# PMIC.net
KiCad netlist of a schematic drawn in Altium Designer
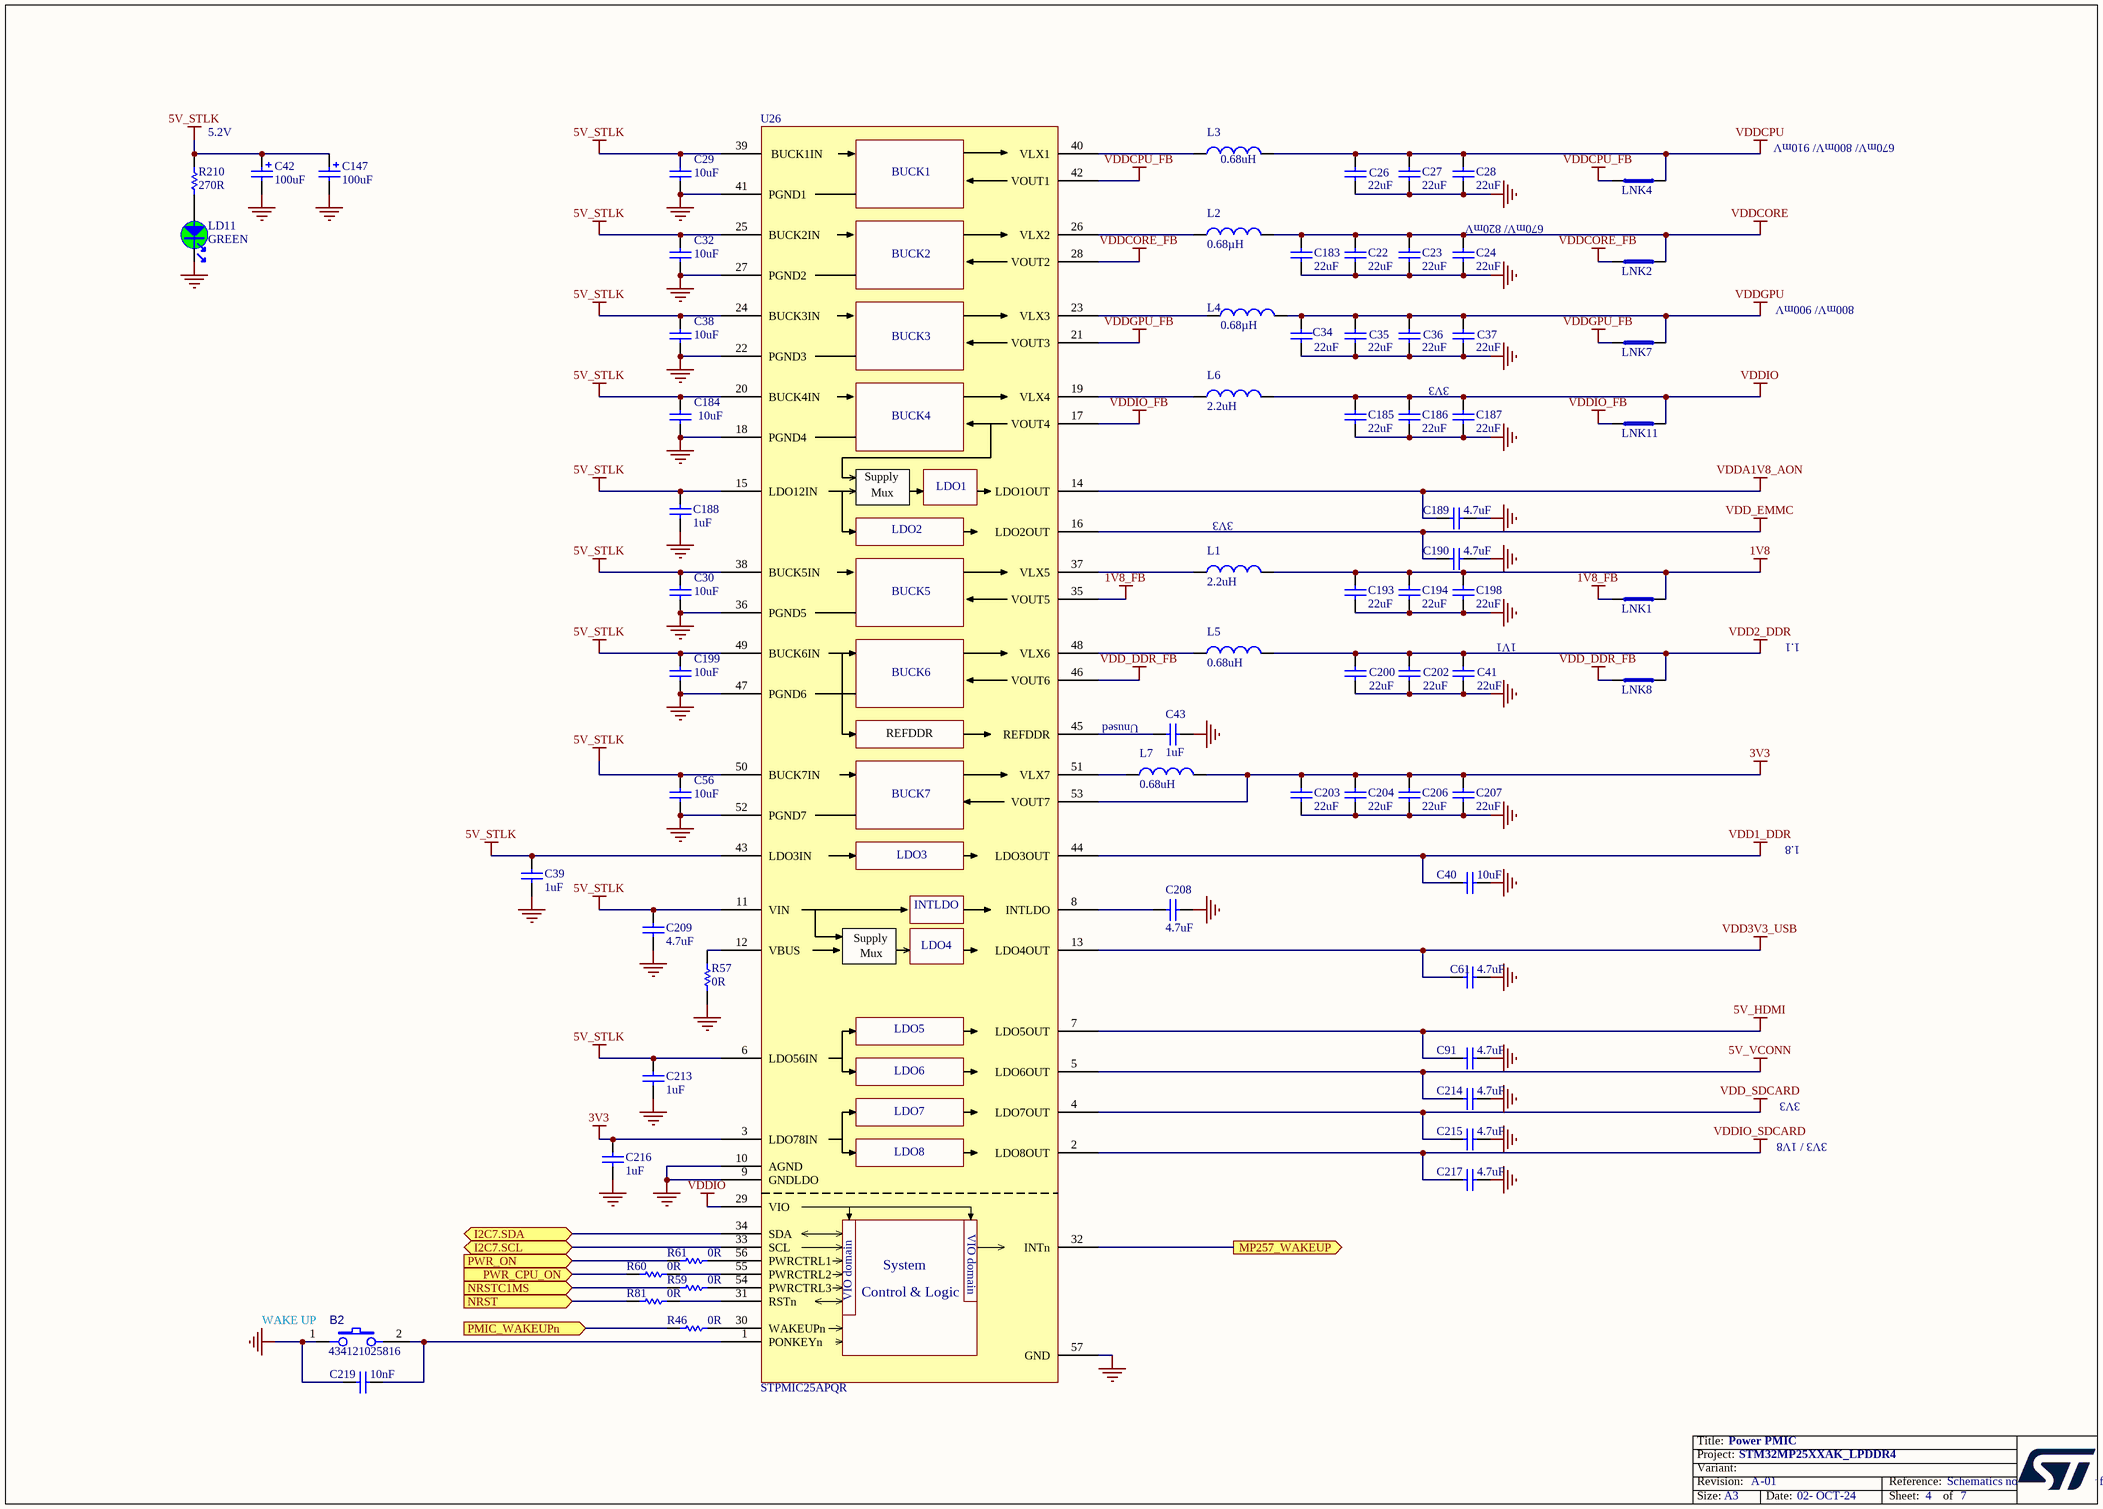
[diagram p0: PMIC.SchDoc]

(export (version "E")
  (design (tool "Eeschema 10.0.6"))
  (components
    (comp (ref "B2")
      (value "434121025816")
      (footprint "SWI_WE_434121025816")
      (description "Switch tactile, SPST-NO, 50mA, 12V, 6x3.8mm")
      (fields
        (field (name "INTERNAL_PART_NUMBER") "MCD-03492")
        (field (name "MANUFACTURER") "WURTH ELEKTRONIC")
      )
      (libsource (lib "MCD_PARTS_database") (part "SW_PUSH_SMD_2P"))
    )
    (comp (ref "C22")
      (value "22uF")
      (footprint "C0603")
      (description "Capacitor, MLCC, 22uF, 6V3, X5R, +/-20%, 0603, T=0,8mm")
      (fields
        (field (name "INTERNAL_PART_NUMBER") "MCD-00100")
        (field (name "MANUFACTURER_PART_NUMBER") "GRM188R60J226MEA0J")
      )
      (libsource (lib "MCD_PARTS_database") (part "Capacitor"))
    )
    (comp (ref "C23")
      (value "22uF")
      (footprint "C0603")
      (description "Capacitor, MLCC, 22uF, 6V3, X5R, +/-20%, 0603, T=0,8mm")
      (fields
        (field (name "INTERNAL_PART_NUMBER") "MCD-00100")
        (field (name "MANUFACTURER_PART_NUMBER") "GRM188R60J226MEA0J")
      )
      (libsource (lib "MCD_PARTS_database") (part "Capacitor"))
    )
    (comp (ref "C24")
      (value "22uF")
      (footprint "C0603")
      (description "Capacitor, MLCC, 22uF, 6V3, X5R, +/-20%, 0603, T=0,8mm")
      (fields
        (field (name "INTERNAL_PART_NUMBER") "MCD-00100")
        (field (name "MANUFACTURER_PART_NUMBER") "GRM188R60J226MEA0J")
      )
      (libsource (lib "MCD_PARTS_database") (part "Capacitor"))
    )
    (comp (ref "C26")
      (value "22uF")
      (footprint "C0603")
      (description "Capacitor, MLCC, 22uF, 6V3, X5R, +/-20%, 0603, T=0,8mm")
      (fields
        (field (name "INTERNAL_PART_NUMBER") "MCD-00100")
        (field (name "MANUFACTURER_PART_NUMBER") "GRM188R60J226MEA0J")
      )
      (libsource (lib "MCD_PARTS_database") (part "Capacitor"))
    )
    (comp (ref "C27")
      (value "22uF")
      (footprint "C0603")
      (description "Capacitor, MLCC, 22uF, 6V3, X5R, +/-20%, 0603, T=0,8mm")
      (fields (field (name "INTERNAL_PART_NUMBER") "MCD-00100") (field (name "MANUFACTURER") "MURATA"))
      (libsource (lib "MCD_PARTS_database") (part "Capacitor"))
    )
    (comp (ref "C28")
      (value "22uF")
      (footprint "C0603")
      (description "Capacitor, MLCC, 22uF, 6V3, X5R, +/-20%, 0603, T=0,8mm")
      (fields (field (name "INTERNAL_PART_NUMBER") "MCD-00100") (field (name "MANUFACTURER") "MURATA"))
      (libsource (lib "MCD_PARTS_database") (part "Capacitor"))
    )
    (comp (ref "C29")
      (value "10uF")
      (footprint "C0603")
      (description "Capacitor, MLCC, 10uF, 10V, X5R, +/-10%, 0603, T=0,8mm")
      (fields
        (field (name "INTERNAL_PART_NUMBER") "MCD-00099")
        (field (name "MANUFACTURER_PART_NUMBER") "GRM188R61A106KE69D")
      )
      (libsource (lib "MCD_PARTS_database") (part "Capacitor"))
    )
    (comp (ref "C30")
      (value "10uF")
      (footprint "C0603")
      (description "Capacitor, MLCC, 10uF, 10V, X5R, +/-10%, 0603, T=0,8mm")
      (fields
        (field (name "INTERNAL_PART_NUMBER") "MCD-00099")
        (field (name "MANUFACTURER_PART_NUMBER") "GRM188R61A106KE69D")
      )
      (libsource (lib "MCD_PARTS_database") (part "Capacitor"))
    )
    (comp (ref "C32")
      (value "10uF")
      (footprint "C0603")
      (description "Capacitor, MLCC, 10uF, 10V, X5R, +/-10%, 0603, T=0,8mm")
      (fields
        (field (name "INTERNAL_PART_NUMBER") "MCD-00099")
        (field (name "MANUFACTURER_PART_NUMBER") "GRM188R61A106KE69D")
      )
      (libsource (lib "MCD_PARTS_database") (part "Capacitor"))
    )
    (comp (ref "C34")
      (value "22uF")
      (footprint "C0603")
      (description "Capacitor, MLCC, 22uF, 6V3, X5R, +/-20%, 0603, T=0,8mm")
      (fields
        (field (name "INTERNAL_PART_NUMBER") "MCD-00100")
        (field (name "MANUFACTURER_PART_NUMBER") "GRM188R60J226MEA0J")
      )
      (libsource (lib "MCD_PARTS_database") (part "Capacitor"))
    )
    (comp (ref "C35")
      (value "22uF")
      (footprint "C0603")
      (description "Capacitor, MLCC, 22uF, 6V3, X5R, +/-20%, 0603, T=0,8mm")
      (fields
        (field (name "INTERNAL_PART_NUMBER") "MCD-00100")
        (field (name "MANUFACTURER_PART_NUMBER") "GRM188R60J226MEA0J")
      )
      (libsource (lib "MCD_PARTS_database") (part "Capacitor"))
    )
    (comp (ref "C36")
      (value "22uF")
      (footprint "C0603")
      (description "Capacitor, MLCC, 22uF, 6V3, X5R, +/-20%, 0603, T=0,8mm")
      (fields
        (field (name "INTERNAL_PART_NUMBER") "MCD-00100")
        (field (name "MANUFACTURER_PART_NUMBER") "GRM188R60J226MEA0J")
      )
      (libsource (lib "MCD_PARTS_database") (part "Capacitor"))
    )
    (comp (ref "C37")
      (value "22uF")
      (footprint "C0603")
      (description "Capacitor, MLCC, 22uF, 6V3, X5R, +/-20%, 0603, T=0,8mm")
      (fields
        (field (name "INTERNAL_PART_NUMBER") "MCD-00100")
        (field (name "MANUFACTURER_PART_NUMBER") "GRM188R60J226MEA0J")
      )
      (libsource (lib "MCD_PARTS_database") (part "Capacitor"))
    )
    (comp (ref "C38")
      (value "10uF")
      (footprint "C0603")
      (description "Capacitor, MLCC, 10uF, 10V, X5R, +/-10%, 0603, T=0,8mm")
      (fields
        (field (name "INTERNAL_PART_NUMBER") "MCD-00099")
        (field (name "MANUFACTURER_PART_NUMBER") "GRM188R61A106KE69D")
      )
      (libsource (lib "MCD_PARTS_database") (part "Capacitor"))
    )
    (comp (ref "C39")
      (value "1uF")
      (footprint "C0402")
      (description "Capacitor, MLCC, 1uF, 25V, X5R, +/-10%, 0402, T=0.5mm")
      (fields (field (name "INTERNAL_PART_NUMBER") "MCD-00095") (field (name "MANUFACTURER") "MURATA"))
      (libsource (lib "MCD_PARTS_database") (part "Capacitor"))
    )
    (comp (ref "C40")
      (value "10uF")
      (footprint "C0402")
      (description "Capacitor, MLCC, 10uF, 6.3V, X5R, +/-20%, 0402, T=0.5mm")
      (fields (field (name "INTERNAL_PART_NUMBER") "MCD-03140") (field (name "MANUFACTURER") "MURATA"))
      (libsource (lib "MCD_PARTS_database") (part "Capacitor"))
    )
    (comp (ref "C41")
      (value "22uF")
      (footprint "C0603")
      (description "Capacitor, MLCC, 22uF, 6V3, X5R, +/-20%, 0603, T=0,8mm")
      (fields
        (field (name "INTERNAL_PART_NUMBER") "MCD-00100")
        (field (name "MANUFACTURER_PART_NUMBER") "GRM188R60J226MEA0J")
      )
      (libsource (lib "MCD_PARTS_database") (part "Capacitor"))
    )
    (comp (ref "C42")
      (value "100uF")
      (footprint "CPOL_TCJ-B_1210_H210")
      (description "Capacitor, Tantalum, 100uF, 6V3, 40mR, +/-20%,  Type_B (3528 metric), T=1.9mm")
      (fields (field (name "INTERNAL_PART_NUMBER") "MCD-01796") (field (name "MANUFACTURER") "AVX"))
      (libsource (lib "MCD_PARTS_database") (part "Cap_POL_TANA"))
    )
    (comp (ref "C43")
      (value "1uF")
      (footprint "C0402")
      (description "Capacitor, MLCC, 1uF, 25V, X5R, +/-10%, 0402, T=0.5mm")
      (fields (field (name "INTERNAL_PART_NUMBER") "MCD-00095") (field (name "MANUFACTURER") "MURATA"))
      (libsource (lib "MCD_PARTS_database") (part "Capacitor"))
    )
    (comp (ref "C56")
      (value "10uF")
      (footprint "C0603")
      (description "Capacitor, MLCC, 10uF, 10V, X5R, +/-10%, 0603, T=0,8mm")
      (fields
        (field (name "INTERNAL_PART_NUMBER") "MCD-00099")
        (field (name "MANUFACTURER_PART_NUMBER") "GRM188R61A106KE69D")
      )
      (libsource (lib "MCD_PARTS_database") (part "Capacitor"))
    )
    (comp (ref "C61")
      (value "4.7uF")
      (footprint "C0402")
      (description "Capacitor, MLCC, 4.7uF, 6V3, X5R, +/-20%, 0402, T=0.5mm")
      (fields
        (field (name "INTERNAL_PART_NUMBER") "MCD-01356")
        (field (name "MANUFACTURER_PART_NUMBER") "GRM155R60J475ME47")
      )
      (libsource (lib "MCD_PARTS_database") (part "Capacitor"))
    )
    (comp (ref "C91")
      (value "4.7uF")
      (footprint "C0402")
      (description "Capacitor, MLCC, 4.7uF, 6V3, X5R, +/-20%, 0402, T=0.5mm")
      (fields
        (field (name "INTERNAL_PART_NUMBER") "MCD-01356")
        (field (name "MANUFACTURER_PART_NUMBER") "GRM155R60J475ME47")
      )
      (libsource (lib "MCD_PARTS_database") (part "Capacitor"))
    )
    (comp (ref "C147")
      (value "100uF")
      (footprint "CPOL_TCJ-B_1210_H210")
      (description "Capacitor, Tantalum, 100uF, 6V3, 40mR, +/-20%,  Type_B (3528 metric), T=1.9mm")
      (fields (field (name "INTERNAL_PART_NUMBER") "MCD-01796") (field (name "MANUFACTURER") "AVX"))
      (libsource (lib "MCD_PARTS_database") (part "Cap_POL_TANA"))
    )
    (comp (ref "C183")
      (value "22uF")
      (footprint "C0603")
      (description "Capacitor, MLCC, 22uF, 6V3, X5R, +/-20%, 0603, T=0,8mm")
      (fields (field (name "INTERNAL_PART_NUMBER") "MCD-00100") (field (name "MANUFACTURER") "MURATA"))
      (libsource (lib "MCD_PARTS_database") (part "Capacitor"))
    )
    (comp (ref "C184")
      (value "10uF")
      (footprint "C0603")
      (description "Capacitor, MLCC, 10uF, 10V, X5R, +/-10%, 0603, T=0,8mm")
      (fields
        (field (name "INTERNAL_PART_NUMBER") "MCD-00099")
        (field (name "MANUFACTURER_PART_NUMBER") "GRM188R61A106KE69D")
      )
      (libsource (lib "MCD_PARTS_database") (part "Capacitor"))
    )
    (comp (ref "C185")
      (value "22uF")
      (footprint "C0805")
      (description "Capacitor, MLCC, 22uF, 10V, X5R, +/-20%, 0805, T=1,25mm")
      (fields (field (name "INTERNAL_PART_NUMBER") "MCD-03139") (field (name "MANUFACTURER") "MURATA"))
      (libsource (lib "MCD_PARTS_database") (part "Capacitor"))
    )
    (comp (ref "C186")
      (value "22uF")
      (footprint "C0805")
      (description "Capacitor, MLCC, 22uF, 10V, X5R, +/-20%, 0805, T=1,25mm")
      (fields (field (name "INTERNAL_PART_NUMBER") "MCD-03139") (field (name "MANUFACTURER") "MURATA"))
      (libsource (lib "MCD_PARTS_database") (part "Capacitor"))
    )
    (comp (ref "C187")
      (value "22uF")
      (footprint "C0805")
      (description "Capacitor, MLCC, 22uF, 10V, X5R, +/-20%, 0805, T=1,25mm")
      (fields (field (name "INTERNAL_PART_NUMBER") "MCD-03139") (field (name "MANUFACTURER") "MURATA"))
      (libsource (lib "MCD_PARTS_database") (part "Capacitor"))
    )
    (comp (ref "C188")
      (value "1uF")
      (footprint "C0402")
      (description "Capacitor, MLCC, 1uF, 25V, X5R, +/-10%, 0402, T=0.5mm")
      (fields (field (name "INTERNAL_PART_NUMBER") "MCD-00095") (field (name "MANUFACTURER") "MURATA"))
      (libsource (lib "MCD_PARTS_database") (part "Capacitor"))
    )
    (comp (ref "C189")
      (value "4.7uF")
      (footprint "C0402")
      (description "Capacitor, MLCC, 4.7uF, 6V3, X5R, +/-20%, 0402, T=0.5mm")
      (fields
        (field (name "INTERNAL_PART_NUMBER") "MCD-01356")
        (field (name "MANUFACTURER_PART_NUMBER") "GRM155R60J475ME47")
      )
      (libsource (lib "MCD_PARTS_database") (part "Capacitor"))
    )
    (comp (ref "C190")
      (value "4.7uF")
      (footprint "C0402")
      (description "Capacitor, MLCC, 4.7uF, 6V3, X5R, +/-20%, 0402, T=0.5mm")
      (fields
        (field (name "INTERNAL_PART_NUMBER") "MCD-01356")
        (field (name "MANUFACTURER_PART_NUMBER") "GRM155R60J475ME47")
      )
      (libsource (lib "MCD_PARTS_database") (part "Capacitor"))
    )
    (comp (ref "C193")
      (value "22uF")
      (footprint "C0805")
      (description "Capacitor, MLCC, 22uF, 10V, X5R, +/-20%, 0805, T=1,25mm")
      (fields (field (name "INTERNAL_PART_NUMBER") "MCD-03139") (field (name "MANUFACTURER") "MURATA"))
      (libsource (lib "MCD_PARTS_database") (part "Capacitor"))
    )
    (comp (ref "C194")
      (value "22uF")
      (footprint "C0805")
      (description "Capacitor, MLCC, 22uF, 10V, X5R, +/-20%, 0805, T=1,25mm")
      (fields (field (name "INTERNAL_PART_NUMBER") "MCD-03139") (field (name "MANUFACTURER") "MURATA"))
      (libsource (lib "MCD_PARTS_database") (part "Capacitor"))
    )
    (comp (ref "C198")
      (value "22uF")
      (footprint "C0805")
      (description "Capacitor, MLCC, 22uF, 10V, X5R, +/-20%, 0805, T=1,25mm")
      (fields (field (name "INTERNAL_PART_NUMBER") "MCD-03139") (field (name "MANUFACTURER") "MURATA"))
      (libsource (lib "MCD_PARTS_database") (part "Capacitor"))
    )
    (comp (ref "C199")
      (value "10uF")
      (footprint "C0603")
      (description "Capacitor, MLCC, 10uF, 10V, X5R, +/-10%, 0603, T=0,8mm")
      (fields
        (field (name "INTERNAL_PART_NUMBER") "MCD-00099")
        (field (name "MANUFACTURER_PART_NUMBER") "GRM188R61A106KE69D")
      )
      (libsource (lib "MCD_PARTS_database") (part "Capacitor"))
    )
    (comp (ref "C200")
      (value "22uF")
      (footprint "C0603")
      (description "Capacitor, MLCC, 22uF, 6V3, X5R, +/-20%, 0603, T=0,8mm")
      (fields
        (field (name "INTERNAL_PART_NUMBER") "MCD-00100")
        (field (name "MANUFACTURER_PART_NUMBER") "GRM188R60J226MEA0J")
      )
      (libsource (lib "MCD_PARTS_database") (part "Capacitor"))
    )
    (comp (ref "C202")
      (value "22uF")
      (footprint "C0603")
      (description "Capacitor, MLCC, 22uF, 6V3, X5R, +/-20%, 0603, T=0,8mm")
      (fields
        (field (name "INTERNAL_PART_NUMBER") "MCD-00100")
        (field (name "MANUFACTURER_PART_NUMBER") "GRM188R60J226MEA0J")
      )
      (libsource (lib "MCD_PARTS_database") (part "Capacitor"))
    )
    (comp (ref "C203")
      (value "22uF")
      (footprint "C0805")
      (description "Capacitor, MLCC, 22uF, 10V, X5R, +/-20%, 0805, T=1,25mm")
      (fields (field (name "INTERNAL_PART_NUMBER") "MCD-03139") (field (name "MANUFACTURER") "MURATA"))
      (libsource (lib "MCD_PARTS_database") (part "Capacitor"))
    )
    (comp (ref "C204")
      (value "22uF")
      (footprint "C0805")
      (description "Capacitor, MLCC, 22uF, 10V, X5R, +/-20%, 0805, T=1,25mm")
      (fields (field (name "INTERNAL_PART_NUMBER") "MCD-03139") (field (name "MANUFACTURER") "MURATA"))
      (libsource (lib "MCD_PARTS_database") (part "Capacitor"))
    )
    (comp (ref "C206")
      (value "22uF")
      (footprint "C0805")
      (description "Capacitor, MLCC, 22uF, 10V, X5R, +/-20%, 0805, T=1,25mm")
      (fields (field (name "INTERNAL_PART_NUMBER") "MCD-03139") (field (name "MANUFACTURER") "MURATA"))
      (libsource (lib "MCD_PARTS_database") (part "Capacitor"))
    )
    (comp (ref "C207")
      (value "22uF")
      (footprint "C0805")
      (description "Capacitor, MLCC, 22uF, 10V, X5R, +/-20%, 0805, T=1,25mm")
      (fields (field (name "INTERNAL_PART_NUMBER") "MCD-03139") (field (name "MANUFACTURER") "MURATA"))
      (libsource (lib "MCD_PARTS_database") (part "Capacitor"))
    )
    (comp (ref "C208")
      (value "4.7uF")
      (footprint "C0402")
      (description "Capacitor, MLCC, 4.7uF, 6V3, X5R, +/-20%, 0402, T=0.5mm")
      (fields
        (field (name "INTERNAL_PART_NUMBER") "MCD-01356")
        (field (name "MANUFACTURER_PART_NUMBER") "GRM155R60J475ME47")
      )
      (libsource (lib "MCD_PARTS_database") (part "Capacitor"))
    )
    (comp (ref "C209")
      (value "4.7uF")
      (footprint "C0402")
      (description "Capacitor, MLCC, 4.7uF, 6V3, X5R, +/-20%, 0402, T=0.5mm")
      (fields
        (field (name "INTERNAL_PART_NUMBER") "MCD-01356")
        (field (name "MANUFACTURER_PART_NUMBER") "GRM155R60J475ME47")
      )
      (libsource (lib "MCD_PARTS_database") (part "Capacitor"))
    )
    (comp (ref "C213")
      (value "1uF")
      (footprint "C0402")
      (description "Capacitor, MLCC, 1uF, 25V, X5R, +/-10%, 0402, T=0.5mm")
      (fields (field (name "INTERNAL_PART_NUMBER") "MCD-00095") (field (name "MANUFACTURER") "MURATA"))
      (libsource (lib "MCD_PARTS_database") (part "Capacitor"))
    )
    (comp (ref "C214")
      (value "4.7uF")
      (footprint "C0402")
      (description "Capacitor, MLCC, 4.7uF, 6V3, X5R, +/-20%, 0402, T=0.5mm")
      (fields
        (field (name "INTERNAL_PART_NUMBER") "MCD-01356")
        (field (name "MANUFACTURER_PART_NUMBER") "GRM155R60J475ME47")
      )
      (libsource (lib "MCD_PARTS_database") (part "Capacitor"))
    )
    (comp (ref "C215")
      (value "4.7uF")
      (footprint "C0402")
      (description "Capacitor, MLCC, 4.7uF, 6V3, X5R, +/-20%, 0402, T=0.5mm")
      (fields
        (field (name "INTERNAL_PART_NUMBER") "MCD-01356")
        (field (name "MANUFACTURER_PART_NUMBER") "GRM155R60J475ME47")
      )
      (libsource (lib "MCD_PARTS_database") (part "Capacitor"))
    )
    (comp (ref "C216")
      (value "1uF")
      (footprint "C0402")
      (description "Capacitor, MLCC, 1uF, 25V, X5R, +/-10%, 0402, T=0.5mm")
      (fields (field (name "INTERNAL_PART_NUMBER") "MCD-00095") (field (name "MANUFACTURER") "MURATA"))
      (libsource (lib "MCD_PARTS_database") (part "Capacitor"))
    )
    (comp (ref "C217")
      (value "4.7uF")
      (footprint "C0402")
      (description "Capacitor, MLCC, 4.7uF, 6V3, X5R, +/-20%, 0402, T=0.5mm")
      (fields
        (field (name "INTERNAL_PART_NUMBER") "MCD-01356")
        (field (name "MANUFACTURER_PART_NUMBER") "GRM155R60J475ME47")
      )
      (libsource (lib "MCD_PARTS_database") (part "Capacitor"))
    )
    (comp (ref "C219")
      (value "10nF")
      (footprint "C0402")
      (description "Capacitor, MLCC, 10nF, 50V, X7R, +/-10%, 0402, T=0.5mm")
      (fields
        (field (name "INTERNAL_PART_NUMBER") "MCD-02198")
        (field (name "MANUFACTURER_PART_NUMBER") "CC0402KRX7R9BB103")
      )
      (libsource (lib "MCD_PARTS_database") (part "Capacitor"))
    )
    (comp (ref "L1")
      (value "2.2uH")
      (footprint "IND_2016_MURATA_LQM2MPN2R2NG0")
      (description "Inductor, 2.2uH, +/-20%, Itemp= 1700mA, Isat= 2400mA, 0R140, 0806, T=1mm")
      (fields (field (name "INTERNAL_PART_NUMBER") "MCD-03143") (field (name "MANUFACTURER") "MURATA"))
      (libsource (lib "MCD_PARTS_database") (part "Inductor"))
    )
    (comp (ref "L2")
      (value "0.68µH")
      (footprint "IND_2520_TOKO_DFE252012P")
      (description "Inductor, 0.68uH, +/-20%, Itemp= 3900mA, Isat= 5400mA, 0R031, 1008, T=1.2mm")
      (fields (field (name "INTERNAL_PART_NUMBER") "MCD-03142") (field (name "MANUFACTURER") "MURATA"))
      (libsource (lib "MCD_PARTS_database") (part "Inductor"))
    )
    (comp (ref "L3")
      (value "0.68uH")
      (footprint "IND_2016_MURATA_LQM2MPN2R2NG0")
      (description "Inductor, 0.68uH, +/-20%, Itemp= 3100mA, Isat= 4300mA, 0R043, 0806, T=1mm")
      (fields (field (name "INTERNAL_PART_NUMBER") "MCD-03141") (field (name "MANUFACTURER") "MURATA"))
      (libsource (lib "MCD_PARTS_database") (part "Inductor"))
    )
    (comp (ref "L4")
      (value "0.68µH")
      (footprint "IND_2520_TOKO_DFE252012P")
      (description "Inductor, 0.68uH, +/-20%, Itemp= 3900mA, Isat= 5400mA, 0R031, 1008, T=1.2mm")
      (fields (field (name "INTERNAL_PART_NUMBER") "MCD-03142") (field (name "MANUFACTURER") "MURATA"))
      (libsource (lib "MCD_PARTS_database") (part "Inductor"))
    )
    (comp (ref "L5")
      (value "0.68uH")
      (footprint "IND_2016_MURATA_LQM2MPN2R2NG0")
      (description "Inductor, 0.68uH, +/-20%, Itemp= 3100mA, Isat= 4300mA, 0R043, 0806, T=1mm")
      (fields (field (name "INTERNAL_PART_NUMBER") "MCD-03141") (field (name "MANUFACTURER") "MURATA"))
      (libsource (lib "MCD_PARTS_database") (part "Inductor"))
    )
    (comp (ref "L6")
      (value "2.2uH")
      (footprint "IND_2016_MURATA_LQM2MPN2R2NG0")
      (description "Inductor, 2.2uH, +/-20%, Itemp= 1700mA, Isat= 2400mA, 0R140, 0806, T=1mm")
      (fields (field (name "INTERNAL_PART_NUMBER") "MCD-03143") (field (name "MANUFACTURER") "MURATA"))
      (libsource (lib "MCD_PARTS_database") (part "Inductor"))
    )
    (comp (ref "L7")
      (value "0.68uH")
      (footprint "IND_2016_MURATA_LQM2MPN2R2NG0")
      (description "Inductor, 0.68uH, +/-20%, Itemp= 3100mA, Isat= 4300mA, 0R043, 0806, T=1mm")
      (fields (field (name "INTERNAL_PART_NUMBER") "MCD-03141") (field (name "MANUFACTURER") "MURATA"))
      (libsource (lib "MCD_PARTS_database") (part "Inductor"))
    )
    (comp (ref "LD11")
      (value "GREEN")
      (footprint "LED_0603_OSRAM_LG-Q396-PS-35_GREEN_1A2K_H0P4")
      (description "LED Green, 0603 SMD, Forward Voltage Typ=2V, Max=2.5V")
      (fields
        (field (name "INTERNAL_PART_NUMBER") "MCD-00588")
        (field (name "MANUFACTURER_PART_NUMBER") "LG Q396-PS-35")
        (field (name "PROVIDED_BY") "SUBCO")
      )
      (libsource (lib "MCD_PARTS_database") (part "LED_green"))
    )
    (comp (ref "LNK1")
      (value "link_200")
      (footprint "LINK200")
      (description "Track link on PCB 200um width for layout routing")
      (fields (field (name "INTERNAL_PART_NUMBER") "MCD-02777"))
      (libsource (lib "MCD_PARTS_database") (part "link_200"))
    )
    (comp (ref "LNK2")
      (value "link_200")
      (footprint "LINK200")
      (description "Track link on PCB 200um width for layout routing")
      (fields (field (name "INTERNAL_PART_NUMBER") "MCD-02777"))
      (libsource (lib "MCD_PARTS_database") (part "link_200"))
    )
    (comp (ref "LNK4")
      (value "link_200")
      (footprint "LINK200")
      (description "Track link on PCB 200um width for layout routing")
      (fields (field (name "INTERNAL_PART_NUMBER") "MCD-02777"))
      (libsource (lib "MCD_PARTS_database") (part "link_200"))
    )
    (comp (ref "LNK7")
      (value "link_200")
      (footprint "LINK200")
      (description "Track link on PCB 200um width for layout routing")
      (fields (field (name "INTERNAL_PART_NUMBER") "MCD-02777"))
      (libsource (lib "MCD_PARTS_database") (part "link_200"))
    )
    (comp (ref "LNK8")
      (value "link_200")
      (footprint "LINK200")
      (description "Track link on PCB 200um width for layout routing")
      (fields (field (name "INTERNAL_PART_NUMBER") "MCD-02777"))
      (libsource (lib "MCD_PARTS_database") (part "link_200"))
    )
    (comp (ref "LNK11")
      (value "link_200")
      (footprint "LINK200")
      (description "Track link on PCB 200um width for layout routing")
      (fields (field (name "INTERNAL_PART_NUMBER") "MCD-02777"))
      (libsource (lib "MCD_PARTS_database") (part "link_200"))
    )
    (comp (ref "R46")
      (value "0R")
      (footprint "R0402")
      (description "Resistor,0R,0402,5%,1/16W")
      (fields
        (field (name "INTERNAL_PART_NUMBER") "MCD-00052")
        (field (name "MANUFACTURER_PART_NUMBER") "RC0402JR-070RL")
        (field (name "PROVIDED_BY") "SUBCO")
      )
      (libsource (lib "MCD_PARTS_database") (part "Resistor"))
    )
    (comp (ref "R57")
      (value "0R")
      (footprint "R0402")
      (description "Resistor,0R,0402,5%,1/16W")
      (fields
        (field (name "INTERNAL_PART_NUMBER") "MCD-00052")
        (field (name "MANUFACTURER_PART_NUMBER") "RC0402JR-070RL")
        (field (name "PROVIDED_BY") "SUBCO")
      )
      (libsource (lib "MCD_PARTS_database") (part "Resistor"))
    )
    (comp (ref "R59")
      (value "0R")
      (footprint "R0402")
      (description "Resistor,0R,0402,5%,1/16W")
      (fields
        (field (name "INTERNAL_PART_NUMBER") "MCD-00052")
        (field (name "MANUFACTURER_PART_NUMBER") "RC0402JR-070RL")
        (field (name "PROVIDED_BY") "SUBCO")
      )
      (libsource (lib "MCD_PARTS_database") (part "Resistor"))
    )
    (comp (ref "R60")
      (value "0R")
      (footprint "R0402")
      (description "Resistor,0R,0402,5%,1/16W")
      (fields
        (field (name "INTERNAL_PART_NUMBER") "MCD-00052")
        (field (name "MANUFACTURER_PART_NUMBER") "RC0402JR-070RL")
        (field (name "PROVIDED_BY") "SUBCO")
      )
      (libsource (lib "MCD_PARTS_database") (part "Resistor"))
    )
    (comp (ref "R61")
      (value "0R")
      (footprint "R0402")
      (description "Resistor,0R,0402,5%,1/16W")
      (fields
        (field (name "INTERNAL_PART_NUMBER") "MCD-00052")
        (field (name "MANUFACTURER_PART_NUMBER") "RC0402JR-070RL")
        (field (name "PROVIDED_BY") "SUBCO")
      )
      (libsource (lib "MCD_PARTS_database") (part "Resistor"))
    )
    (comp (ref "R81")
      (value "0R")
      (footprint "R0402")
      (description "Resistor,0R,0402,5%,1/16W")
      (fields
        (field (name "INTERNAL_PART_NUMBER") "MCD-00052")
        (field (name "MANUFACTURER_PART_NUMBER") "RC0402JR-070RL")
        (field (name "PROVIDED_BY") "SUBCO")
      )
      (libsource (lib "MCD_PARTS_database") (part "Resistor"))
    )
    (comp (ref "R210")
      (value "270R")
      (footprint "R0402")
      (description "Resistor,270R,0402,1%,1/16W")
      (fields
        (field (name "INTERNAL_PART_NUMBER") "MCD-00441")
        (field (name "MANUFACTURER_PART_NUMBER") "RC0402FR-07270RL")
        (field (name "PROVIDED_BY") "SUBCO")
      )
      (libsource (lib "MCD_PARTS_database") (part "Resistor"))
    )
    (comp (ref "U26")
      (value "STPMIC25APQR")
      (footprint "ICC_QFN56-EPAD_6P5X6P5_P040")
      (description "STPMIC2")
      (fields
        (field (name "INTERNAL_PART_NUMBER") "MCD-03000")
        (field (name "MANUFACTURER") "STMICROELECTRONICS")
      )
      (libsource (lib "MCD_PARTS_database") (part "STPMIC2"))
    )
  )
  (nets
    (net (code "1") (name "/I2C7.SCL") (class "Default")
      (node (ref "U26") (pin "33") (pinfunction "SCL_33") (pintype "passive"))
    )
    (net (code "2") (name "/I2C7.SDA") (class "Default")
      (node (ref "U26") (pin "34") (pinfunction "SDA_34") (pintype "passive"))
    )
    (net (code "3") (name "/MP257_WAKEUP") (class "Default")
      (node (ref "U26") (pin "32") (pinfunction "INTn_32") (pintype "passive"))
    )
    (net (code "4") (name "/NRST") (class "Default")
      (node (ref "R81") (pin "1") (pinfunction "1_1") (pintype "passive"))
    )
    (net (code "5") (name "/NRSTC1MS") (class "Default")
      (node (ref "R59") (pin "1") (pinfunction "1_1") (pintype "passive"))
    )
    (net (code "6") (name "/PMIC_WAKEUPn") (class "Default")
      (node (ref "R46") (pin "1") (pinfunction "1_1") (pintype "passive"))
    )
    (net (code "7") (name "/PWR_CPU_ON") (class "Default")
      (node (ref "R60") (pin "1") (pinfunction "1_1") (pintype "passive"))
    )
    (net (code "8") (name "/PWR_ON") (class "Default")
      (node (ref "R61") (pin "1") (pinfunction "1_1") (pintype "passive"))
    )
    (net (code "9") (name "1V8") (class "Default")
      (node (ref "C193") (pin "2") (pinfunction "2_2") (pintype "passive"))
      (node (ref "C194") (pin "2") (pinfunction "2_2") (pintype "passive"))
      (node (ref "C198") (pin "2") (pinfunction "2_2") (pintype "passive"))
      (node (ref "L1") (pin "2") (pinfunction "2_2") (pintype "passive"))
      (node (ref "LNK1") (pin "2") (pinfunction "2_2") (pintype "passive"))
    )
    (net (code "10") (name "1V8_FB") (class "Default")
      (node (ref "LNK1") (pin "1") (pinfunction "1_1") (pintype "passive"))
      (node (ref "U26") (pin "35") (pinfunction "VOUT5_35") (pintype "passive"))
    )
    (net (code "11") (name "3V3") (class "Default")
      (node (ref "C203") (pin "2") (pinfunction "2_2") (pintype "passive"))
      (node (ref "C204") (pin "2") (pinfunction "2_2") (pintype "passive"))
      (node (ref "C206") (pin "2") (pinfunction "2_2") (pintype "passive"))
      (node (ref "C207") (pin "2") (pinfunction "2_2") (pintype "passive"))
      (node (ref "C216") (pin "2") (pinfunction "2_2") (pintype "passive"))
      (node (ref "L7") (pin "2") (pinfunction "2_2") (pintype "passive"))
      (node (ref "U26") (pin "3") (pinfunction "LDO78IN_3") (pintype "passive"))
      (node (ref "U26") (pin "53") (pinfunction "VOUT7_53") (pintype "passive"))
    )
    (net (code "12") (name "5V_HDMI") (class "Default")
      (node (ref "C91") (pin "1") (pinfunction "1_1") (pintype "passive"))
      (node (ref "U26") (pin "7") (pinfunction "LDO5OUT_7") (pintype "passive"))
    )
    (net (code "13") (name "5V_STLK") (class "Default")
      (node (ref "C147") (pin "1") (pinfunction "1_1") (pintype "passive"))
      (node (ref "C184") (pin "2") (pinfunction "2_2") (pintype "passive"))
      (node (ref "C188") (pin "2") (pinfunction "2_2") (pintype "passive"))
      (node (ref "C199") (pin "2") (pinfunction "2_2") (pintype "passive"))
      (node (ref "C209") (pin "2") (pinfunction "2_2") (pintype "passive"))
      (node (ref "C213") (pin "2") (pinfunction "2_2") (pintype "passive"))
      (node (ref "C29") (pin "2") (pinfunction "2_2") (pintype "passive"))
      (node (ref "C30") (pin "2") (pinfunction "2_2") (pintype "passive"))
      (node (ref "C32") (pin "2") (pinfunction "2_2") (pintype "passive"))
      (node (ref "C38") (pin "2") (pinfunction "2_2") (pintype "passive"))
      (node (ref "C39") (pin "2") (pinfunction "2_2") (pintype "passive"))
      (node (ref "C42") (pin "1") (pinfunction "1_1") (pintype "passive"))
      (node (ref "C56") (pin "2") (pinfunction "2_2") (pintype "passive"))
      (node (ref "R210") (pin "1") (pinfunction "1_1") (pintype "passive"))
      (node (ref "U26") (pin "11") (pinfunction "VIN_11") (pintype "passive"))
      (node (ref "U26") (pin "15") (pinfunction "LDO12IN_15") (pintype "passive"))
      (node (ref "U26") (pin "20") (pinfunction "BUCK4IN_20") (pintype "passive"))
      (node (ref "U26") (pin "24") (pinfunction "BUCK3IN_24") (pintype "passive"))
      (node (ref "U26") (pin "25") (pinfunction "BUCK2IN_25") (pintype "passive"))
      (node (ref "U26") (pin "38") (pinfunction "BUCK5IN_38") (pintype "passive"))
      (node (ref "U26") (pin "39") (pinfunction "BUCK1IN_39") (pintype "passive"))
      (node (ref "U26") (pin "43") (pinfunction "LDO3IN_43") (pintype "passive"))
      (node (ref "U26") (pin "49") (pinfunction "BUCK6IN_49") (pintype "passive"))
      (node (ref "U26") (pin "50") (pinfunction "BUCK7IN_50") (pintype "passive"))
      (node (ref "U26") (pin "6") (pinfunction "LDO56IN_6") (pintype "passive"))
    )
    (net (code "14") (name "5V_VCONN") (class "Default")
      (node (ref "C214") (pin "1") (pinfunction "1_1") (pintype "passive"))
      (node (ref "U26") (pin "5") (pinfunction "LDO6OUT_5") (pintype "passive"))
    )
    (net (code "15") (name "GND") (class "Default")
      (node (ref "B2") (pin "1") (pinfunction "1_1") (pintype "passive"))
      (node (ref "C147") (pin "2") (pinfunction "2_2") (pintype "passive"))
      (node (ref "C183") (pin "1") (pinfunction "1_1") (pintype "passive"))
      (node (ref "C184") (pin "1") (pinfunction "1_1") (pintype "passive"))
      (node (ref "C185") (pin "1") (pinfunction "1_1") (pintype "passive"))
      (node (ref "C186") (pin "1") (pinfunction "1_1") (pintype "passive"))
      (node (ref "C187") (pin "1") (pinfunction "1_1") (pintype "passive"))
      (node (ref "C188") (pin "1") (pinfunction "1_1") (pintype "passive"))
      (node (ref "C189") (pin "1") (pinfunction "1_1") (pintype "passive"))
      (node (ref "C190") (pin "2") (pinfunction "2_2") (pintype "passive"))
      (node (ref "C193") (pin "1") (pinfunction "1_1") (pintype "passive"))
      (node (ref "C194") (pin "1") (pinfunction "1_1") (pintype "passive"))
      (node (ref "C198") (pin "1") (pinfunction "1_1") (pintype "passive"))
      (node (ref "C199") (pin "1") (pinfunction "1_1") (pintype "passive"))
      (node (ref "C200") (pin "1") (pinfunction "1_1") (pintype "passive"))
      (node (ref "C202") (pin "1") (pinfunction "1_1") (pintype "passive"))
      (node (ref "C203") (pin "1") (pinfunction "1_1") (pintype "passive"))
      (node (ref "C204") (pin "1") (pinfunction "1_1") (pintype "passive"))
      (node (ref "C206") (pin "1") (pinfunction "1_1") (pintype "passive"))
      (node (ref "C207") (pin "1") (pinfunction "1_1") (pintype "passive"))
      (node (ref "C208") (pin "2") (pinfunction "2_2") (pintype "passive"))
      (node (ref "C209") (pin "1") (pinfunction "1_1") (pintype "passive"))
      (node (ref "C213") (pin "1") (pinfunction "1_1") (pintype "passive"))
      (node (ref "C214") (pin "2") (pinfunction "2_2") (pintype "passive"))
      (node (ref "C215") (pin "2") (pinfunction "2_2") (pintype "passive"))
      (node (ref "C216") (pin "1") (pinfunction "1_1") (pintype "passive"))
      (node (ref "C217") (pin "2") (pinfunction "2_2") (pintype "passive"))
      (node (ref "C219") (pin "1") (pinfunction "1_1") (pintype "passive"))
      (node (ref "C22") (pin "1") (pinfunction "1_1") (pintype "passive"))
      (node (ref "C23") (pin "1") (pinfunction "1_1") (pintype "passive"))
      (node (ref "C24") (pin "1") (pinfunction "1_1") (pintype "passive"))
      (node (ref "C26") (pin "1") (pinfunction "1_1") (pintype "passive"))
      (node (ref "C27") (pin "1") (pinfunction "1_1") (pintype "passive"))
      (node (ref "C28") (pin "1") (pinfunction "1_1") (pintype "passive"))
      (node (ref "C29") (pin "1") (pinfunction "1_1") (pintype "passive"))
      (node (ref "C30") (pin "1") (pinfunction "1_1") (pintype "passive"))
      (node (ref "C32") (pin "1") (pinfunction "1_1") (pintype "passive"))
      (node (ref "C34") (pin "1") (pinfunction "1_1") (pintype "passive"))
      (node (ref "C35") (pin "1") (pinfunction "1_1") (pintype "passive"))
      (node (ref "C36") (pin "1") (pinfunction "1_1") (pintype "passive"))
      (node (ref "C37") (pin "1") (pinfunction "1_1") (pintype "passive"))
      (node (ref "C38") (pin "1") (pinfunction "1_1") (pintype "passive"))
      (node (ref "C39") (pin "1") (pinfunction "1_1") (pintype "passive"))
      (node (ref "C40") (pin "1") (pinfunction "1_1") (pintype "passive"))
      (node (ref "C41") (pin "1") (pinfunction "1_1") (pintype "passive"))
      (node (ref "C42") (pin "2") (pinfunction "2_2") (pintype "passive"))
      (node (ref "C43") (pin "1") (pinfunction "1_1") (pintype "passive"))
      (node (ref "C56") (pin "1") (pinfunction "1_1") (pintype "passive"))
      (node (ref "C61") (pin "1") (pinfunction "1_1") (pintype "passive"))
      (node (ref "C91") (pin "2") (pinfunction "2_2") (pintype "passive"))
      (node (ref "LD11") (pin "2") (pintype "passive"))
      (node (ref "R57") (pin "1") (pinfunction "1_1") (pintype "passive"))
      (node (ref "U26") (pin "10") (pinfunction "AGND_10") (pintype "passive"))
      (node (ref "U26") (pin "18") (pinfunction "PGND4_18") (pintype "passive"))
      (node (ref "U26") (pin "22") (pinfunction "PGND3_22") (pintype "passive"))
      (node (ref "U26") (pin "27") (pinfunction "PGND2_27") (pintype "passive"))
      (node (ref "U26") (pin "36") (pinfunction "PGND5_36") (pintype "passive"))
      (node (ref "U26") (pin "41") (pinfunction "PGND1_41") (pintype "passive"))
      (node (ref "U26") (pin "47") (pinfunction "PGND6_47") (pintype "passive"))
      (node (ref "U26") (pin "52") (pinfunction "PGND7_52") (pintype "passive"))
      (node (ref "U26") (pin "57") (pinfunction "GND_57") (pintype "passive"))
      (node (ref "U26") (pin "9") (pinfunction "GNDLDO_9") (pintype "passive"))
    )
    (net (code "16") (name "Net-(LD11-Pad1)") (class "Default")
      (node (ref "LD11") (pin "1") (pintype "passive"))
      (node (ref "R210") (pin "2") (pinfunction "2_2") (pintype "passive"))
    )
    (net (code "17") (name "Net-(U26-INTLDO)") (class "Default")
      (node (ref "C208") (pin "1") (pinfunction "1_1") (pintype "passive"))
      (node (ref "U26") (pin "8") (pinfunction "INTLDO_8") (pintype "passive"))
    )
    (net (code "18") (name "Net-(U26-PONKEYn)") (class "Default")
      (node (ref "B2") (pin "2") (pinfunction "2_2") (pintype "passive"))
      (node (ref "C219") (pin "2") (pinfunction "2_2") (pintype "passive"))
      (node (ref "U26") (pin "1") (pinfunction "PONKEYn_1") (pintype "passive"))
    )
    (net (code "19") (name "Net-(U26-PWRCTRL1)") (class "Default")
      (node (ref "R61") (pin "2") (pinfunction "2_2") (pintype "passive"))
      (node (ref "U26") (pin "56") (pinfunction "PWRCTRL1_56") (pintype "passive"))
    )
    (net (code "20") (name "Net-(U26-PWRCTRL2)") (class "Default")
      (node (ref "R60") (pin "2") (pinfunction "2_2") (pintype "passive"))
      (node (ref "U26") (pin "55") (pinfunction "PWRCTRL2_55") (pintype "passive"))
    )
    (net (code "21") (name "Net-(U26-PWRCTRL3)") (class "Default")
      (node (ref "R59") (pin "2") (pinfunction "2_2") (pintype "passive"))
      (node (ref "U26") (pin "54") (pinfunction "PWRCTRL3_54") (pintype "passive"))
    )
    (net (code "22") (name "Net-(U26-REFDDR)") (class "Default")
      (node (ref "C43") (pin "2") (pinfunction "2_2") (pintype "passive"))
      (node (ref "U26") (pin "45") (pinfunction "REFDDR_45") (pintype "passive"))
    )
    (net (code "23") (name "Net-(U26-RSTn)") (class "Default")
      (node (ref "R81") (pin "2") (pinfunction "2_2") (pintype "passive"))
      (node (ref "U26") (pin "31") (pinfunction "RSTn_31") (pintype "passive"))
    )
    (net (code "24") (name "Net-(U26-VBUS)") (class "Default")
      (node (ref "R57") (pin "2") (pinfunction "2_2") (pintype "passive"))
      (node (ref "U26") (pin "12") (pinfunction "VBUS_12") (pintype "passive"))
    )
    (net (code "25") (name "Net-(U26-VLX1)") (class "Default")
      (node (ref "L3") (pin "1") (pinfunction "1_1") (pintype "passive"))
      (node (ref "U26") (pin "40") (pinfunction "VLX1_40") (pintype "passive"))
    )
    (net (code "26") (name "Net-(U26-VLX2)") (class "Default")
      (node (ref "L2") (pin "1") (pinfunction "1_1") (pintype "passive"))
      (node (ref "U26") (pin "26") (pinfunction "VLX2_26") (pintype "passive"))
    )
    (net (code "27") (name "Net-(U26-VLX3)") (class "Default")
      (node (ref "L4") (pin "1") (pinfunction "1_1") (pintype "passive"))
      (node (ref "U26") (pin "23") (pinfunction "VLX3_23") (pintype "passive"))
    )
    (net (code "28") (name "Net-(U26-VLX4)") (class "Default")
      (node (ref "L6") (pin "1") (pinfunction "1_1") (pintype "passive"))
      (node (ref "U26") (pin "19") (pinfunction "VLX4_19") (pintype "passive"))
    )
    (net (code "29") (name "Net-(U26-VLX5)") (class "Default")
      (node (ref "L1") (pin "1") (pinfunction "1_1") (pintype "passive"))
      (node (ref "U26") (pin "37") (pinfunction "VLX5_37") (pintype "passive"))
    )
    (net (code "30") (name "Net-(U26-VLX6)") (class "Default")
      (node (ref "L5") (pin "1") (pinfunction "1_1") (pintype "passive"))
      (node (ref "U26") (pin "48") (pinfunction "VLX6_48") (pintype "passive"))
    )
    (net (code "31") (name "Net-(U26-VLX7)") (class "Default")
      (node (ref "L7") (pin "1") (pinfunction "1_1") (pintype "passive"))
      (node (ref "U26") (pin "51") (pinfunction "VLX7_51") (pintype "passive"))
    )
    (net (code "32") (name "Net-(U26-WAKEUPn)") (class "Default")
      (node (ref "R46") (pin "2") (pinfunction "2_2") (pintype "passive"))
      (node (ref "U26") (pin "30") (pinfunction "WAKEUPn_30") (pintype "passive"))
    )
    (net (code "33") (name "VDD1_DDR") (class "Default")
      (node (ref "C40") (pin "2") (pinfunction "2_2") (pintype "passive"))
      (node (ref "U26") (pin "44") (pinfunction "LDO3OUT_44") (pintype "passive"))
    )
    (net (code "34") (name "VDD2_DDR") (class "Default")
      (node (ref "C200") (pin "2") (pinfunction "2_2") (pintype "passive"))
      (node (ref "C202") (pin "2") (pinfunction "2_2") (pintype "passive"))
      (node (ref "C41") (pin "2") (pinfunction "2_2") (pintype "passive"))
      (node (ref "L5") (pin "2") (pinfunction "2_2") (pintype "passive"))
      (node (ref "LNK8") (pin "2") (pinfunction "2_2") (pintype "passive"))
    )
    (net (code "35") (name "VDD3V3_USB") (class "Default")
      (node (ref "C61") (pin "2") (pinfunction "2_2") (pintype "passive"))
      (node (ref "U26") (pin "13") (pinfunction "LDO4OUT_13") (pintype "passive"))
    )
    (net (code "36") (name "VDDA1V8_AON") (class "Default")
      (node (ref "C189") (pin "2") (pinfunction "2_2") (pintype "passive"))
      (node (ref "U26") (pin "14") (pinfunction "LDO1OUT_14") (pintype "passive"))
    )
    (net (code "37") (name "VDDCORE") (class "Default")
      (node (ref "C183") (pin "2") (pinfunction "2_2") (pintype "passive"))
      (node (ref "C22") (pin "2") (pinfunction "2_2") (pintype "passive"))
      (node (ref "C23") (pin "2") (pinfunction "2_2") (pintype "passive"))
      (node (ref "C24") (pin "2") (pinfunction "2_2") (pintype "passive"))
      (node (ref "L2") (pin "2") (pinfunction "2_2") (pintype "passive"))
      (node (ref "LNK2") (pin "2") (pinfunction "2_2") (pintype "passive"))
    )
    (net (code "38") (name "VDDCORE_FB") (class "Default")
      (node (ref "LNK2") (pin "1") (pinfunction "1_1") (pintype "passive"))
      (node (ref "U26") (pin "28") (pinfunction "VOUT2_28") (pintype "passive"))
    )
    (net (code "39") (name "VDDCPU") (class "Default")
      (node (ref "C26") (pin "2") (pinfunction "2_2") (pintype "passive"))
      (node (ref "C27") (pin "2") (pinfunction "2_2") (pintype "passive"))
      (node (ref "C28") (pin "2") (pinfunction "2_2") (pintype "passive"))
      (node (ref "L3") (pin "2") (pinfunction "2_2") (pintype "passive"))
      (node (ref "LNK4") (pin "1") (pinfunction "1_1") (pintype "passive"))
    )
    (net (code "40") (name "VDDCPU_FB") (class "Default")
      (node (ref "LNK4") (pin "2") (pinfunction "2_2") (pintype "passive"))
      (node (ref "U26") (pin "42") (pinfunction "VOUT1_42") (pintype "passive"))
    )
    (net (code "41") (name "VDDGPU") (class "Default")
      (node (ref "C34") (pin "2") (pinfunction "2_2") (pintype "passive"))
      (node (ref "C35") (pin "2") (pinfunction "2_2") (pintype "passive"))
      (node (ref "C36") (pin "2") (pinfunction "2_2") (pintype "passive"))
      (node (ref "C37") (pin "2") (pinfunction "2_2") (pintype "passive"))
      (node (ref "L4") (pin "2") (pinfunction "2_2") (pintype "passive"))
      (node (ref "LNK7") (pin "2") (pinfunction "2_2") (pintype "passive"))
    )
    (net (code "42") (name "VDDGPU_FB") (class "Default")
      (node (ref "LNK7") (pin "1") (pinfunction "1_1") (pintype "passive"))
      (node (ref "U26") (pin "21") (pinfunction "VOUT3_21") (pintype "passive"))
    )
    (net (code "43") (name "VDDIO") (class "Default")
      (node (ref "C185") (pin "2") (pinfunction "2_2") (pintype "passive"))
      (node (ref "C186") (pin "2") (pinfunction "2_2") (pintype "passive"))
      (node (ref "C187") (pin "2") (pinfunction "2_2") (pintype "passive"))
      (node (ref "L6") (pin "2") (pinfunction "2_2") (pintype "passive"))
      (node (ref "LNK11") (pin "2") (pinfunction "2_2") (pintype "passive"))
      (node (ref "U26") (pin "29") (pinfunction "VIO_29") (pintype "passive"))
    )
    (net (code "44") (name "VDDIO_FB") (class "Default")
      (node (ref "LNK11") (pin "1") (pinfunction "1_1") (pintype "passive"))
      (node (ref "U26") (pin "17") (pinfunction "VOUT4_17") (pintype "passive"))
    )
    (net (code "45") (name "VDDIO_SDCARD") (class "Default")
      (node (ref "C217") (pin "1") (pinfunction "1_1") (pintype "passive"))
      (node (ref "U26") (pin "2") (pinfunction "LDO8OUT_2") (pintype "passive"))
    )
    (net (code "46") (name "VDD_DDR_FB") (class "Default")
      (node (ref "LNK8") (pin "1") (pinfunction "1_1") (pintype "passive"))
      (node (ref "U26") (pin "46") (pinfunction "VOUT6_46") (pintype "passive"))
    )
    (net (code "47") (name "VDD_EMMC") (class "Default")
      (node (ref "C190") (pin "1") (pinfunction "1_1") (pintype "passive"))
      (node (ref "U26") (pin "16") (pinfunction "LDO2OUT_16") (pintype "passive"))
    )
    (net (code "48") (name "VDD_SDCARD") (class "Default")
      (node (ref "C215") (pin "1") (pinfunction "1_1") (pintype "passive"))
      (node (ref "U26") (pin "4") (pinfunction "LDO7OUT_4") (pintype "passive"))
    )
  )
)
